# 7segement2digits1badidea-mk-5_0.net
KiCad netlist of a schematic drawn in EAGLE
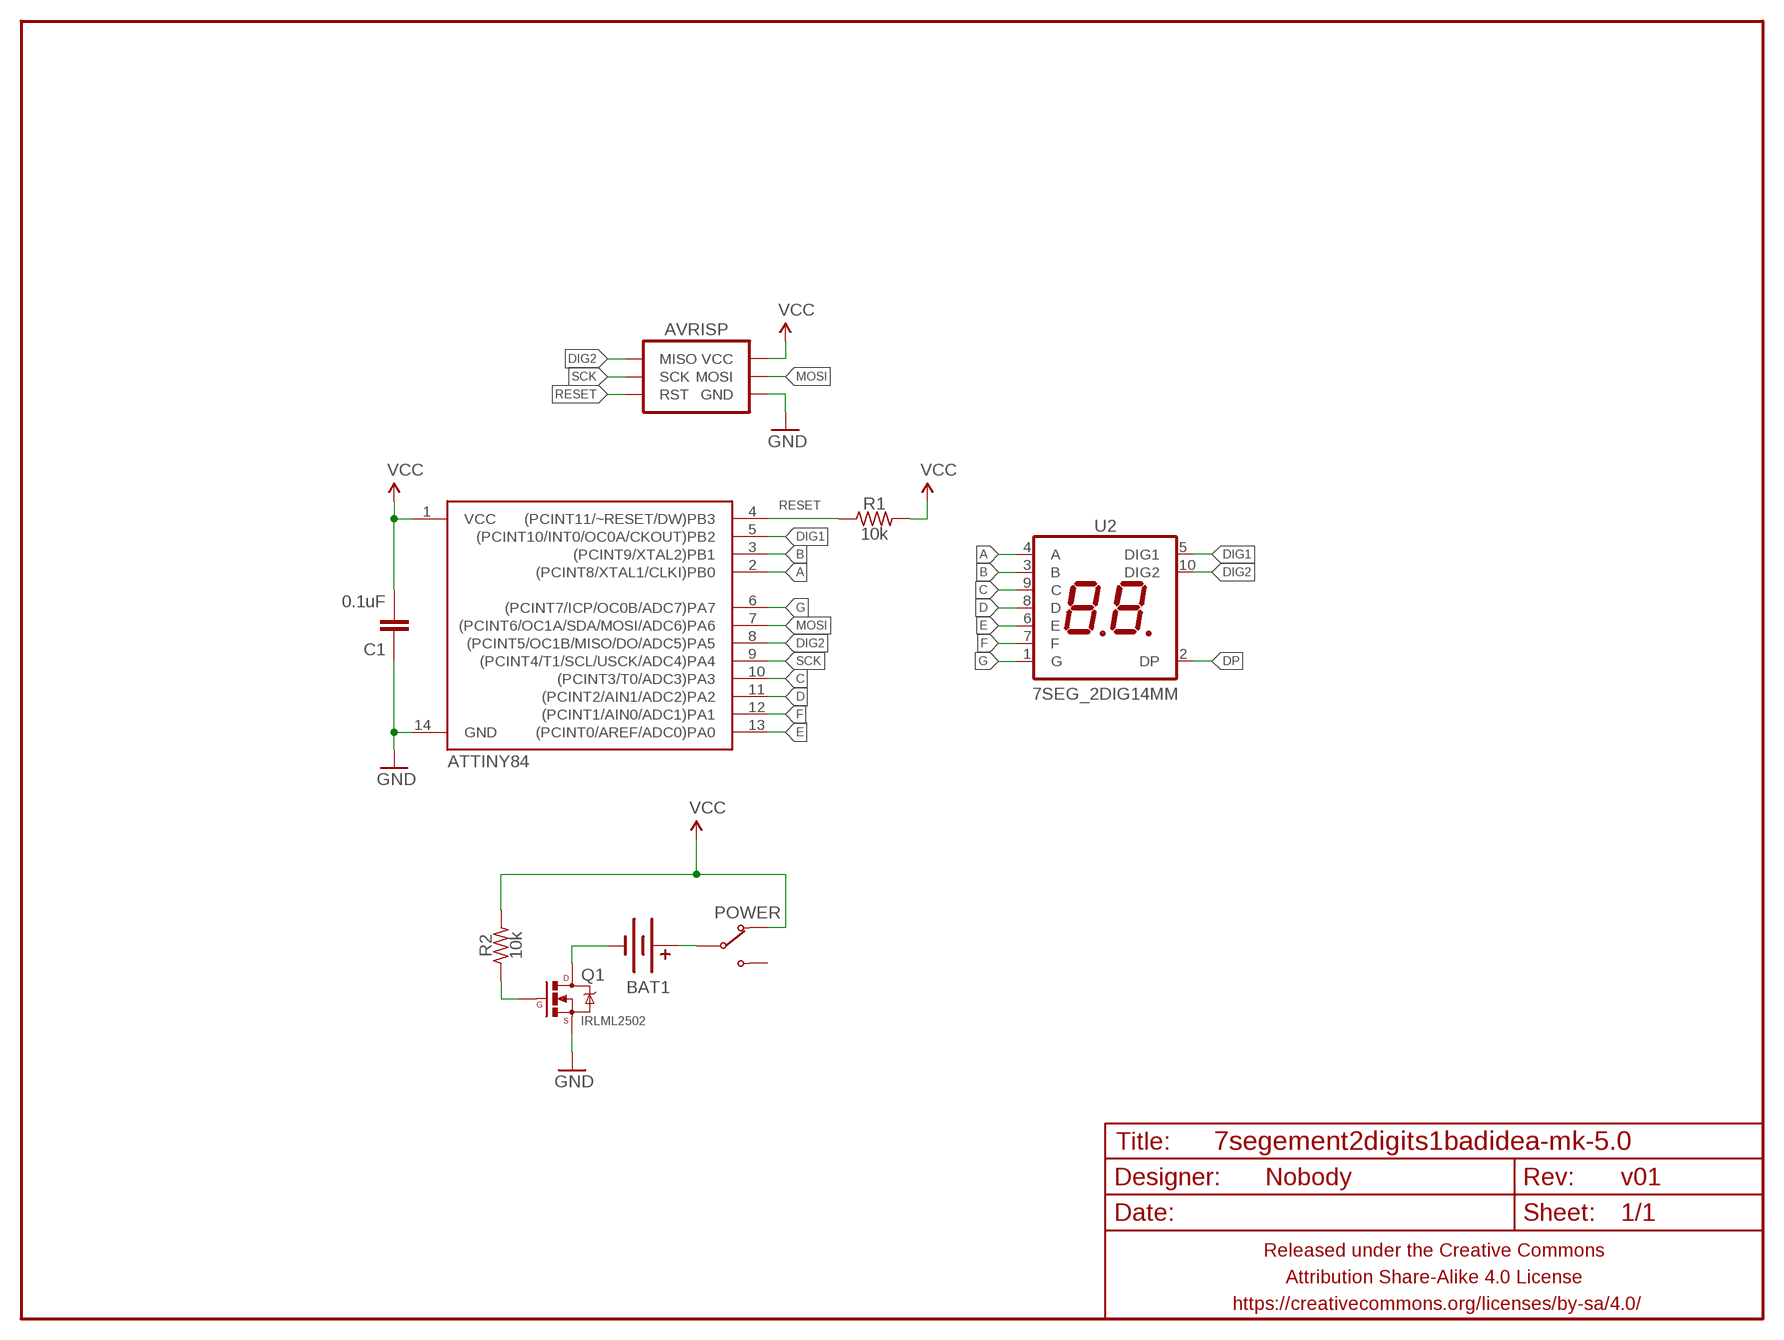
[diagram p0: schematic, sheet 1]

(export (version "E")
  (design (tool "Eeschema 10.0.6"))
  (components
    (comp (ref "AVRISP")
      (value "AVR_SPI_PRG_6PTH")
      (footprint "eagle-import:2X3")
      (libsource (lib "eagle-import") (part "AVR_SPI_PRG_6PTH"))
    )
    (comp (ref "BAT1")
      (value "BATTERY20PTH_TOPLOAD")
      (footprint "eagle-import:BATTCON_20MM_PTH_TOPLOAD")
      (libsource (lib "eagle-import") (part "BATTERY20PTH_TOPLOAD"))
    )
    (comp (ref "C1")
      (value "0.1uF")
      (footprint "eagle-import:C0805")
      (libsource (lib "eagle-import") (part "CAPACITOR-CERAMICC0805"))
    )
    (comp (ref "FRAME1")
      (value "FRAME-LETTERNO_PACKAGE")
      (footprint "eagle-import:DUMMY")
      (fields (field (name "DESIGNER") "Nobody"))
      (libsource (lib "eagle-import") (part "FRAME-LETTERNO_PACKAGE"))
    )
    (comp (ref "POWER")
      (value "SWITCH-SPDTPTH-RA-2.54MM")
      (footprint "eagle-import:SPDT-RA-2.54MM")
      (libsource (lib "eagle-import") (part "SWITCH-SPDTPTH-RA-2.54MM"))
    )
    (comp (ref "Q1")
      (value "IRLML2502")
      (footprint "eagle-import:SOT23")
      (libsource (lib "eagle-import") (part "MOSFET-NCHANNELIRLML2502"))
    )
    (comp (ref "R1")
      (value "10k")
      (footprint "eagle-import:R0805")
      (libsource (lib "eagle-import") (part "RESISTORR0805"))
    )
    (comp (ref "R2")
      (value "10k")
      (footprint "eagle-import:R0805")
      (libsource (lib "eagle-import") (part "RESISTORR0805"))
    )
    (comp (ref "U1")
      (value "ATTINY84")
      (footprint "eagle-import:SO14")
      (libsource (lib "eagle-import") (part "ATTINY84"))
    )
    (comp (ref "U2")
      (value "7SEG_2DIG14MM")
      (footprint "eagle-import:7SEG_2DIG_14MM")
      (libsource (lib "eagle-import") (part "7SEG_2DIG14MM"))
    )
  )
  (nets
    (net (code "1") (name "A") (class "Default")
      (node (ref "U1") (pin "2") (pinfunction "(PCINT8/XTAL1/CLKI)PB0_2") (pintype "bidirectional"))
      (node (ref "U2") (pin "4") (pinfunction "A_4") (pintype "passive"))
    )
    (net (code "2") (name "B") (class "Default")
      (node (ref "U1") (pin "3") (pinfunction "(PCINT9/XTAL2)PB1_3") (pintype "bidirectional"))
      (node (ref "U2") (pin "3") (pinfunction "B_3") (pintype "passive"))
    )
    (net (code "3") (name "C") (class "Default")
      (node (ref "U1") (pin "10") (pinfunction "(PCINT3/T0/ADC3)PA3_10") (pintype "bidirectional"))
      (node (ref "U2") (pin "9") (pinfunction "C_9") (pintype "passive"))
    )
    (net (code "4") (name "D") (class "Default")
      (node (ref "U1") (pin "11") (pinfunction "(PCINT2/AIN1/ADC2)PA2_11") (pintype "bidirectional"))
      (node (ref "U2") (pin "8") (pinfunction "D_8") (pintype "passive"))
    )
    (net (code "5") (name "DIG1") (class "Default")
      (node (ref "U1") (pin "5") (pinfunction "(PCINT10/INT0/OC0A/CKOUT)PB2_5") (pintype "bidirectional"))
      (node (ref "U2") (pin "5") (pinfunction "DIG1_5") (pintype "passive"))
    )
    (net (code "6") (name "DIG2") (class "Default")
      (node (ref "AVRISP") (pin "1") (pinfunction "MISO_1") (pintype "passive"))
      (node (ref "U1") (pin "8") (pinfunction "(PCINT5/OC1B/MISO/DO/ADC5)PA5_8") (pintype "bidirectional"))
      (node (ref "U2") (pin "10") (pinfunction "DIG2_10") (pintype "passive"))
    )
    (net (code "7") (name "DP") (class "Default")
      (node (ref "U2") (pin "2") (pinfunction "DP_2") (pintype "passive"))
    )
    (net (code "8") (name "E") (class "Default")
      (node (ref "U1") (pin "13") (pinfunction "(PCINT0/AREF/ADC0)PA0_13") (pintype "bidirectional"))
      (node (ref "U2") (pin "6") (pinfunction "E_6") (pintype "passive"))
    )
    (net (code "9") (name "F") (class "Default")
      (node (ref "U1") (pin "12") (pinfunction "(PCINT1/AIN0/ADC1)PA1_12") (pintype "bidirectional"))
      (node (ref "U2") (pin "7") (pinfunction "F_7") (pintype "passive"))
    )
    (net (code "10") (name "G") (class "Default")
      (node (ref "U1") (pin "6") (pinfunction "(PCINT7/ICP/OC0B/ADC7)PA7_6") (pintype "bidirectional"))
      (node (ref "U2") (pin "1") (pinfunction "G_1") (pintype "passive"))
    )
    (net (code "11") (name "GND") (class "Default")
      (node (ref "AVRISP") (pin "6") (pinfunction "GND_6") (pintype "passive"))
      (node (ref "C1") (pin "1") (pinfunction "1_1") (pintype "passive"))
      (node (ref "Q1") (pin "2") (pinfunction "S_2") (pintype "passive"))
      (node (ref "U1") (pin "14") (pinfunction "GND_14") (pintype "bidirectional"))
    )
    (net (code "12") (name "MOSI") (class "Default")
      (node (ref "AVRISP") (pin "4") (pinfunction "MOSI_4") (pintype "passive"))
      (node (ref "U1") (pin "7") (pinfunction "(PCINT6/OC1A/SDA/MOSI/ADC6)PA6_7") (pintype "bidirectional"))
    )
    (net (code "13") (name "Net-(POWER-COM)") (class "Default")
      (node (ref "BAT1") (pin "+") (pinfunction "+_+") (pintype "power_in"))
      (node (ref "POWER") (pin "2") (pinfunction "COM_2") (pintype "passive"))
    )
    (net (code "14") (name "Net-(Q1-D)") (class "Default")
      (node (ref "BAT1") (pin "-") (pinfunction "-_-") (pintype "power_in"))
      (node (ref "Q1") (pin "3") (pinfunction "D_3") (pintype "passive"))
    )
    (net (code "15") (name "Net-(Q1-G)") (class "Default")
      (node (ref "Q1") (pin "1") (pinfunction "G_1") (pintype "passive"))
      (node (ref "R2") (pin "1") (pinfunction "1_1") (pintype "passive"))
    )
    (net (code "16") (name "RESET") (class "Default")
      (node (ref "AVRISP") (pin "5") (pinfunction "RST_5") (pintype "passive"))
      (node (ref "R1") (pin "1") (pinfunction "1_1") (pintype "passive"))
      (node (ref "U1") (pin "4") (pinfunction "(PCINT11/~{RESET/DW})PB3_4") (pintype "bidirectional"))
    )
    (net (code "17") (name "SCK") (class "Default")
      (node (ref "AVRISP") (pin "3") (pinfunction "SCK_3") (pintype "passive"))
      (node (ref "U1") (pin "9") (pinfunction "(PCINT4/T1/SCL/USCK/ADC4)PA4_9") (pintype "bidirectional"))
    )
    (net (code "18") (name "VCC") (class "Default")
      (node (ref "AVRISP") (pin "2") (pinfunction "VCC_2") (pintype "passive"))
      (node (ref "C1") (pin "2") (pinfunction "2_2") (pintype "passive"))
      (node (ref "POWER") (pin "1") (pinfunction "NC_1") (pintype "passive"))
      (node (ref "R1") (pin "2") (pinfunction "2_2") (pintype "passive"))
      (node (ref "R2") (pin "2") (pinfunction "2_2") (pintype "passive"))
      (node (ref "U1") (pin "1") (pinfunction "VCC_1") (pintype "bidirectional"))
    )
    (net (code "19") (name "unconnected-(POWER-NO-Pad3)") (class "Default")
      (node (ref "POWER") (pin "3") (pinfunction "NO_3") (pintype "passive"))
    )
  )
)
